# System_Input.net
KiCad netlist of a schematic drawn in Altium Designer
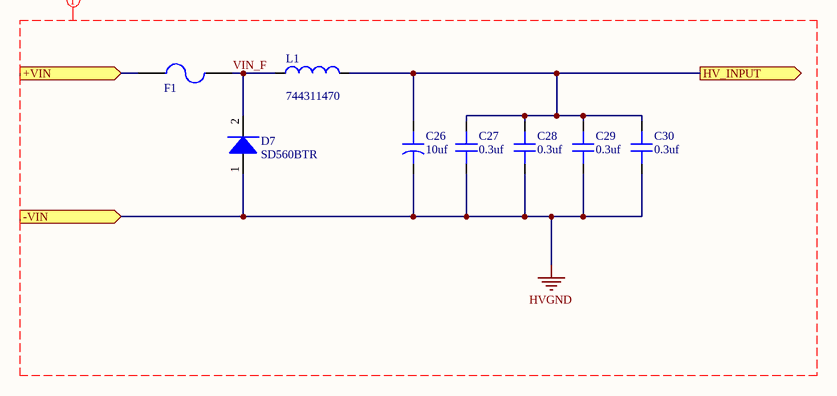
[diagram p0: System Input.SchDoc]

(export (version "E")
  (design (tool "Eeschema 10.0.6"))
  (components
    (comp (ref "C26")
      (value "10uf")
      (footprint "CAP AL TH D10 L5 H30")
      (description "10µF 500V Aluminum Electrolytic Capacitors Radial, Can  8000 Hrs @ 105°C")
      (fields
        (field (name "MFRPARTNO") "EKXJ501ELL100MJ30S")
        (field (name "Comment") "Capacitor Electrolytic 10uf 500V CAP D10_31.5")
        (field (name "CREATED_BY") "Nick Mah")
      )
      (libsource (lib "Altium-Lib") (part "Capacitor_Electrolytic"))
    )
    (comp (ref "C27")
      (value "0.3uf")
      (footprint "CAP 1812/4532 2.8MM")
      (description "Null")
      (fields
        (field (name "TOLERANCE") "10%")
        (field (name "MFRPARTNO") "C4532X7T2J304K250KA")
        (field (name "CREATED_BY") "Jason Zhou")
      )
      (libsource (lib "Altium-Lib") (part "Capacitor"))
    )
    (comp (ref "C28")
      (value "0.3uf")
      (footprint "CAP 1812/4532 2.8MM")
      (description "Null")
      (fields
        (field (name "TOLERANCE") "10%")
        (field (name "MFRPARTNO") "C4532X7T2J304K250KA")
        (field (name "CREATED_BY") "Jason Zhou")
      )
      (libsource (lib "Altium-Lib") (part "Capacitor"))
    )
    (comp (ref "C29")
      (value "0.3uf")
      (footprint "CAP 1812/4532 2.8MM")
      (description "Null")
      (fields
        (field (name "TOLERANCE") "10%")
        (field (name "MFRPARTNO") "C4532X7T2J304K250KA")
        (field (name "CREATED_BY") "Jason Zhou")
      )
      (libsource (lib "Altium-Lib") (part "Capacitor"))
    )
    (comp (ref "C30")
      (value "0.3uf")
      (footprint "CAP 1812/4532 2.8MM")
      (description "Null")
      (fields
        (field (name "TOLERANCE") "10%")
        (field (name "MFRPARTNO") "C4532X7T2J304K250KA")
        (field (name "CREATED_BY") "Jason Zhou")
      )
      (libsource (lib "Altium-Lib") (part "Capacitor"))
    )
    (comp (ref "D7")
      (value "SD560BTR")
      (footprint "DO214AA_ SD560BTR")
      (description "Diode Standard 600V 5A Surface Mount SMB")
      (fields (field (name "CREATED_BY") "Jason Zhou"))
      (libsource (lib "Altium-Lib") (part "DIODE"))
    )
    (comp (ref "F1")
      (value "Fuse")
      (footprint "04853,15DR")
      (fields (field (name "MFRPARTNO") "04853.15DR") (field (name "CREATED_BY") "Jason Zhou"))
      (libsource (lib "Altium-Lib") (part "Fuse"))
    )
    (comp (ref "L1")
      (value "~")
      (footprint "744311470")
      (description "4.7uH Wirewound Inductor 6A 19.5 mOhm Nonstandard")
      (fields
        (field (name "MFRPARTNO") "744311470")
        (field (name "TOLERANCE") "20%")
        (field (name "CREATED_BY") "Jason Zhou")
      )
      (libsource (lib "Altium-Lib") (part "Inductor"))
    )
  )
  (nets
    (net (code "1") (name "/+VIN") (class "Default")
      (node (ref "F1") (pin "1") (pinfunction "1_1") (pintype "passive"))
    )
    (net (code "2") (name "/HV_INPUT") (class "Default")
      (node (ref "C26") (pin "1") (pinfunction "1_1") (pintype "passive"))
      (node (ref "C27") (pin "2") (pinfunction "2_2") (pintype "passive"))
      (node (ref "C28") (pin "2") (pinfunction "2_2") (pintype "passive"))
      (node (ref "C29") (pin "2") (pinfunction "2_2") (pintype "passive"))
      (node (ref "C30") (pin "2") (pinfunction "2_2") (pintype "passive"))
      (node (ref "L1") (pin "2") (pinfunction "2_2") (pintype "passive"))
    )
    (net (code "3") (name "/VIN_F") (class "Default")
      (node (ref "D7") (pin "2") (pinfunction "K_2") (pintype "passive"))
      (node (ref "F1") (pin "2") (pinfunction "2_2") (pintype "passive"))
      (node (ref "L1") (pin "1") (pinfunction "1_1") (pintype "passive"))
    )
    (net (code "4") (name "HVGND") (class "Default")
      (node (ref "C26") (pin "2") (pinfunction "2_2") (pintype "passive"))
      (node (ref "C27") (pin "1") (pinfunction "1_1") (pintype "passive"))
      (node (ref "C28") (pin "1") (pinfunction "1_1") (pintype "passive"))
      (node (ref "C29") (pin "1") (pinfunction "1_1") (pintype "passive"))
      (node (ref "C30") (pin "1") (pinfunction "1_1") (pintype "passive"))
      (node (ref "D7") (pin "1") (pinfunction "A_1") (pintype "passive"))
    )
  )
)
